# SubPSSerialControl.net
KiCad netlist of a schematic drawn in Altium Designer
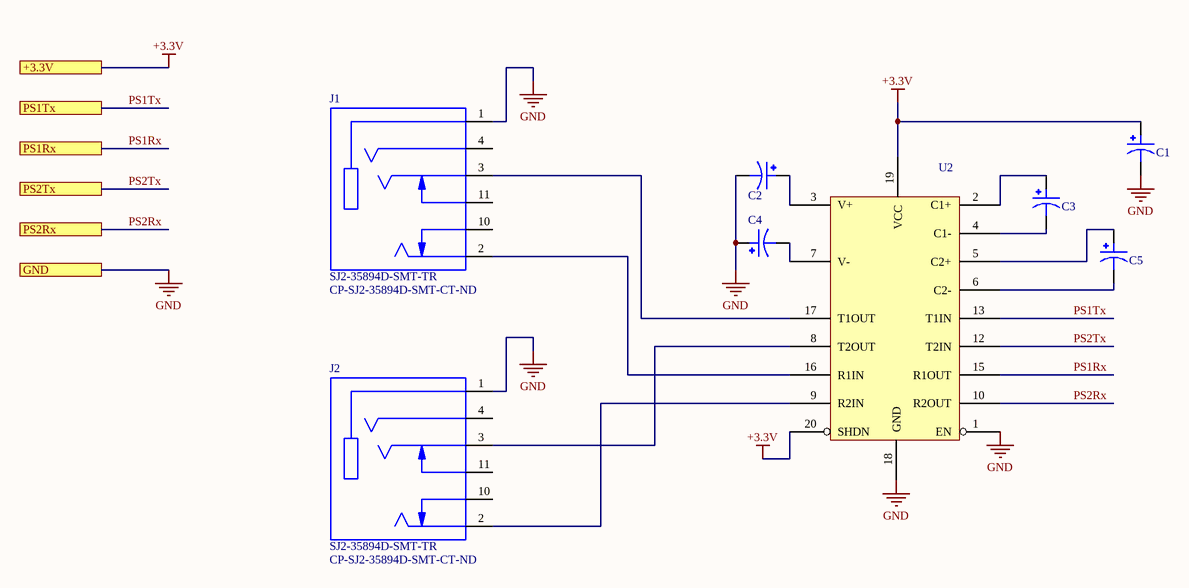
[diagram p0: SubPSSerialControl.SchDoc]

(export (version "E")
  (design (tool "Eeschema 10.0.6"))
  (components
    (comp (ref "C1")
      (value "T491A104K050AT")
      (footprint "C1206")
      (description "Tantalium")
      (libsource (lib "Afshin Library") (part "Cap_1206"))
    )
    (comp (ref "C2")
      (value "T491A104K050AT")
      (footprint "C1206")
      (description "Tantalium")
      (libsource (lib "") (part "Cap_1206_2"))
    )
    (comp (ref "C3")
      (value "T491A104K050AT")
      (footprint "C1206")
      (description "Tantalium")
      (libsource (lib "Afshin Library") (part "Cap_1206"))
    )
    (comp (ref "C4")
      (value "T491A104K050AT")
      (footprint "C1206")
      (description "Tantalium")
      (libsource (lib "") (part "Cap_1206_1"))
    )
    (comp (ref "C5")
      (value "T491A104K050AT")
      (footprint "C1206")
      (description "Tantalium")
      (libsource (lib "Afshin Library") (part "Cap_1206"))
    )
    (comp (ref "J1")
      (value "SJ2-35894D-SMT-TR")
      (footprint "CUI_SJ2-35894D-SMT-TR")
      (description "3.5 mm, Stereo, Right Angle, Surface Mount _SMT_, Audio Jack Connector")
      (fields
        (field (name "MF") "CUI Devices")
        (field (name "SUPPLIER PART NUMBER 1") "CP-SJ2-35894D-SMT-CT-ND")
      )
      (libsource (lib "Afshin Library") (part "SJ2-35894D-SMT-TR"))
    )
    (comp (ref "J2")
      (value "SJ2-35894D-SMT-TR")
      (footprint "CUI_SJ2-35894D-SMT-TR")
      (description "3.5 mm, Stereo, Right Angle, Surface Mount _SMT_, Audio Jack Connector")
      (fields
        (field (name "MF") "CUI Devices")
        (field (name "SUPPLIER PART NUMBER 1") "CP-SJ2-35894D-SMT-CT-ND")
      )
      (libsource (lib "Afshin Library") (part "SJ2-35894D-SMT-TR"))
    )
    (comp (ref "U2")
      (value "SP3222ECY-L/TR")
      (footprint "20-TSSOP")
      (libsource (lib "Afshin Library") (part "SP3222e"))
    )
  )
  (nets
    (net (code "1") (name "+3.3V") (class "Default")
      (node (ref "C1") (pin "1") (pinfunction "POS_1") (pintype "passive"))
      (node (ref "U2") (pin "19") (pinfunction "VCC_19") (pintype "passive"))
      (node (ref "U2") (pin "20") (pinfunction "SHDN_20") (pintype "passive"))
    )
    (net (code "2") (name "/PS1Rx") (class "Default")
      (node (ref "U2") (pin "15") (pinfunction "R1OUT_15") (pintype "passive"))
    )
    (net (code "3") (name "/PS1Tx") (class "Default")
      (node (ref "U2") (pin "13") (pinfunction "T1IN_13") (pintype "passive"))
    )
    (net (code "4") (name "/PS2Rx") (class "Default")
      (node (ref "U2") (pin "10") (pinfunction "R2OUT_10") (pintype "passive"))
    )
    (net (code "5") (name "/PS2Tx") (class "Default")
      (node (ref "U2") (pin "12") (pinfunction "T2IN_12") (pintype "passive"))
    )
    (net (code "6") (name "GND") (class "Default")
      (node (ref "C1") (pin "2") (pinfunction "NEG_2") (pintype "passive"))
      (node (ref "C2") (pin "2") (pinfunction "NEG_2") (pintype "passive"))
      (node (ref "C4") (pin "1") (pinfunction "POS_1") (pintype "passive"))
      (node (ref "J1") (pin "1") (pinfunction "SLEEVE_1") (pintype "passive"))
      (node (ref "J2") (pin "1") (pinfunction "SLEEVE_1") (pintype "passive"))
      (node (ref "U2") (pin "1") (pinfunction "EN_1") (pintype "passive"))
      (node (ref "U2") (pin "18") (pinfunction "GND_18") (pintype "passive"))
    )
    (net (code "7") (name "Net-(C2-POS)") (class "Default")
      (node (ref "C2") (pin "1") (pinfunction "POS_1") (pintype "passive"))
      (node (ref "U2") (pin "3") (pinfunction "V+_3") (pintype "passive"))
    )
    (net (code "8") (name "Net-(C3-NEG)") (class "Default")
      (node (ref "C3") (pin "2") (pinfunction "NEG_2") (pintype "passive"))
      (node (ref "U2") (pin "4") (pinfunction "C1-_4") (pintype "passive"))
    )
    (net (code "9") (name "Net-(C3-POS)") (class "Default")
      (node (ref "C3") (pin "1") (pinfunction "POS_1") (pintype "passive"))
      (node (ref "U2") (pin "2") (pinfunction "C1+_2") (pintype "passive"))
    )
    (net (code "10") (name "Net-(C4-NEG)") (class "Default")
      (node (ref "C4") (pin "2") (pinfunction "NEG_2") (pintype "passive"))
      (node (ref "U2") (pin "7") (pinfunction "V-_7") (pintype "passive"))
    )
    (net (code "11") (name "Net-(C5-NEG)") (class "Default")
      (node (ref "C5") (pin "2") (pinfunction "NEG_2") (pintype "passive"))
      (node (ref "U2") (pin "6") (pinfunction "C2-_6") (pintype "passive"))
    )
    (net (code "12") (name "Net-(C5-POS)") (class "Default")
      (node (ref "C5") (pin "1") (pinfunction "POS_1") (pintype "passive"))
      (node (ref "U2") (pin "5") (pinfunction "C2+_5") (pintype "passive"))
    )
    (net (code "13") (name "Net-(J1-RING1)") (class "Default")
      (node (ref "J1") (pin "3") (pinfunction "RING1_3") (pintype "passive"))
      (node (ref "U2") (pin "17") (pinfunction "T1OUT_17") (pintype "passive"))
    )
    (net (code "14") (name "Net-(J1-TIP)") (class "Default")
      (node (ref "J1") (pin "2") (pinfunction "TIP_2") (pintype "passive"))
      (node (ref "U2") (pin "16") (pinfunction "R1IN_16") (pintype "passive"))
    )
    (net (code "15") (name "Net-(J2-RING1)") (class "Default")
      (node (ref "J2") (pin "3") (pinfunction "RING1_3") (pintype "passive"))
      (node (ref "U2") (pin "8") (pinfunction "T2OUT_8") (pintype "passive"))
    )
    (net (code "16") (name "Net-(J2-TIP)") (class "Default")
      (node (ref "J2") (pin "2") (pinfunction "TIP_2") (pintype "passive"))
      (node (ref "U2") (pin "9") (pinfunction "R2IN_9") (pintype "passive"))
    )
    (net (code "17") (name "unconnected-(J1-RING1_SWITCH-Pad11)") (class "Default")
      (node (ref "J1") (pin "11") (pinfunction "RING1_SWITCH_11") (pintype "passive"))
    )
    (net (code "18") (name "unconnected-(J1-RING2-Pad4)") (class "Default")
      (node (ref "J1") (pin "4") (pinfunction "RING2_4") (pintype "passive"))
    )
    (net (code "19") (name "unconnected-(J1-TIP_SWITCH-Pad10)") (class "Default")
      (node (ref "J1") (pin "10") (pinfunction "TIP_SWITCH_10") (pintype "passive"))
    )
    (net (code "20") (name "unconnected-(J2-RING1_SWITCH-Pad11)") (class "Default")
      (node (ref "J2") (pin "11") (pinfunction "RING1_SWITCH_11") (pintype "passive"))
    )
    (net (code "21") (name "unconnected-(J2-RING2-Pad4)") (class "Default")
      (node (ref "J2") (pin "4") (pinfunction "RING2_4") (pintype "passive"))
    )
    (net (code "22") (name "unconnected-(J2-TIP_SWITCH-Pad10)") (class "Default")
      (node (ref "J2") (pin "10") (pinfunction "TIP_SWITCH_10") (pintype "passive"))
    )
  )
)
